# gtjennings_4.net
KiCad netlist of a schematic drawn in EAGLE
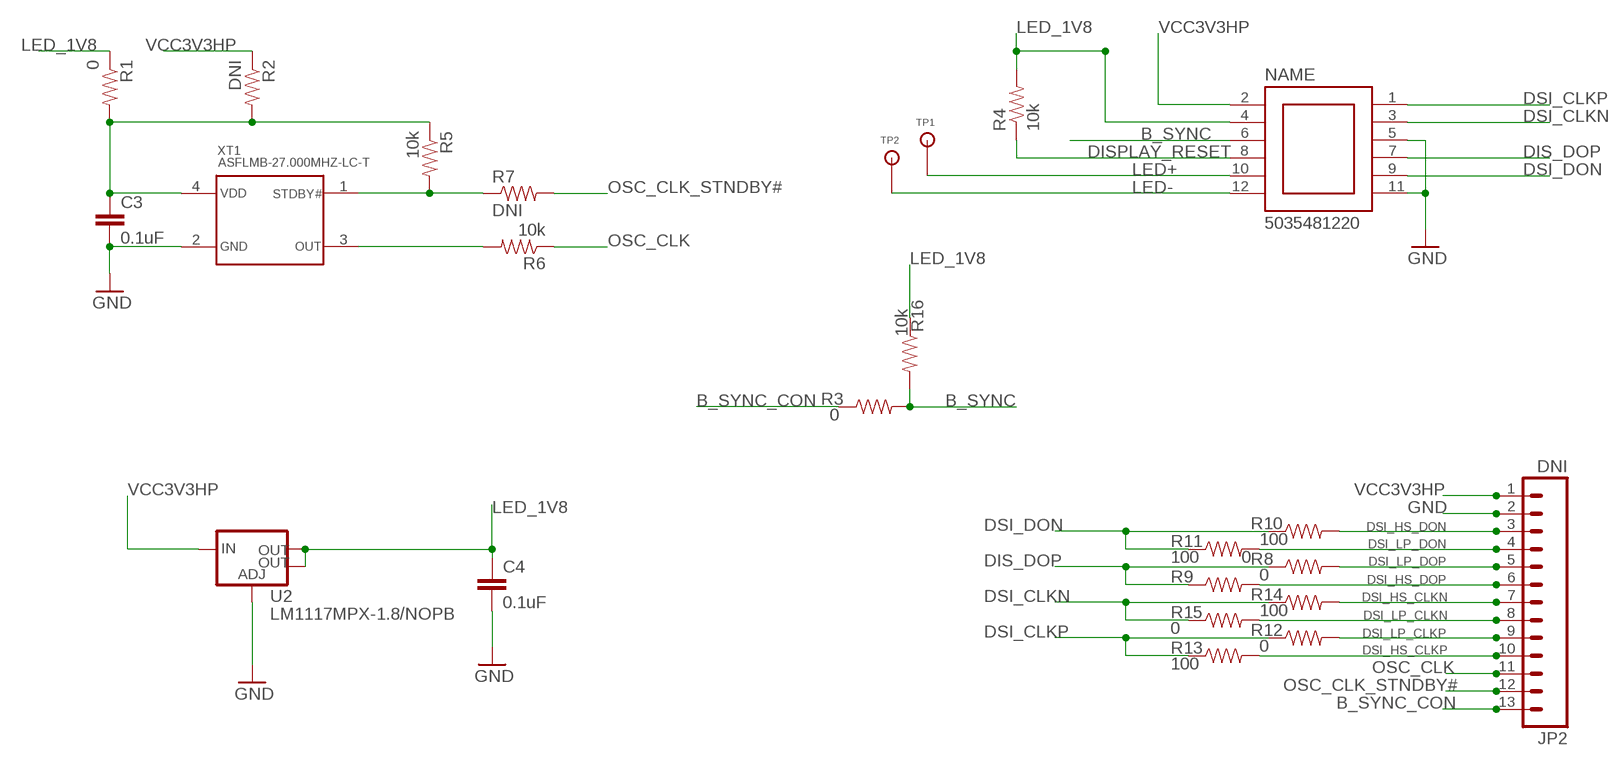
[diagram p0: schematic, sheet 1]

(export (version "E")
  (design (tool "Eeschema 10.0.6"))
  (components
    (comp (ref "C3")
      (value "0.1uF")
      (footprint "eagle-import:0402-CAP")
      (libsource (lib "eagle-import") (part "CAP0402-CAP"))
    )
    (comp (ref "C4")
      (value "0.1uF")
      (footprint "eagle-import:0402-CAP")
      (libsource (lib "eagle-import") (part "CAP0402-CAP"))
    )
    (comp (ref "JP1")
      (value "5035481220")
      (footprint "eagle-import:5035481220")
      (libsource (lib "eagle-import") (part "5035481220"))
    )
    (comp (ref "JP2")
      (value "DNI")
      (footprint "eagle-import:1X13")
      (libsource (lib "eagle-import") (part "M13"))
    )
    (comp (ref "R1")
      (value "0")
      (footprint "eagle-import:0402-RES")
      (libsource (lib "eagle-import") (part "RESISTOR0402"))
    )
    (comp (ref "R2")
      (value "DNI")
      (footprint "eagle-import:0402-RES")
      (libsource (lib "eagle-import") (part "RESISTOR0402"))
    )
    (comp (ref "R3")
      (value "0")
      (footprint "eagle-import:0402-RES")
      (libsource (lib "eagle-import") (part "RESISTOR0402"))
    )
    (comp (ref "R4")
      (value "10k")
      (footprint "eagle-import:0402-RES")
      (libsource (lib "eagle-import") (part "RESISTOR0402"))
    )
    (comp (ref "R5")
      (value "10k")
      (footprint "eagle-import:0402-RES")
      (libsource (lib "eagle-import") (part "RESISTOR0402"))
    )
    (comp (ref "R6")
      (value "10k")
      (footprint "eagle-import:0402-RES")
      (libsource (lib "eagle-import") (part "RESISTOR0402"))
    )
    (comp (ref "R7")
      (value "DNI")
      (footprint "eagle-import:0402-RES")
      (libsource (lib "eagle-import") (part "RESISTOR0402"))
    )
    (comp (ref "R8")
      (value "0")
      (footprint "eagle-import:0402-RES")
      (libsource (lib "eagle-import") (part "RESISTOR0402"))
    )
    (comp (ref "R9")
      (value "100")
      (footprint "eagle-import:0402-RES")
      (libsource (lib "eagle-import") (part "RESISTOR0402"))
    )
    (comp (ref "R10")
      (value "100")
      (footprint "eagle-import:0402-RES")
      (libsource (lib "eagle-import") (part "RESISTOR0402"))
    )
    (comp (ref "R11")
      (value "0")
      (footprint "eagle-import:0402-RES")
      (libsource (lib "eagle-import") (part "RESISTOR0402"))
    )
    (comp (ref "R12")
      (value "0")
      (footprint "eagle-import:0402-RES")
      (libsource (lib "eagle-import") (part "RESISTOR0402"))
    )
    (comp (ref "R13")
      (value "100")
      (footprint "eagle-import:0402-RES")
      (libsource (lib "eagle-import") (part "RESISTOR0402"))
    )
    (comp (ref "R14")
      (value "100")
      (footprint "eagle-import:0402-RES")
      (libsource (lib "eagle-import") (part "RESISTOR0402"))
    )
    (comp (ref "R15")
      (value "0")
      (footprint "eagle-import:0402-RES")
      (libsource (lib "eagle-import") (part "RESISTOR0402"))
    )
    (comp (ref "R16")
      (value "10k")
      (footprint "eagle-import:0402-RES")
      (libsource (lib "eagle-import") (part "RESISTOR0402"))
    )
    (comp (ref "TP1") (value "TP") (footprint "eagle-import:TP") (libsource (lib "eagle-import") (part "TP")))
    (comp (ref "TP2") (value "TP") (footprint "eagle-import:TP") (libsource (lib "eagle-import") (part "TP")))
    (comp (ref "U2")
      (value "LM1117MPX-1.8/NOPB")
      (footprint "eagle-import:SOT223")
      (libsource (lib "eagle-import") (part "V_REG_LM1117SOT223"))
    )
    (comp (ref "XT1")
      (value "ASFLMB-27.000MHZ-LC-T")
      (footprint "eagle-import:ASFLMB-27.000MHZ-LC-T")
      (libsource (lib "eagle-import") (part "ASFLMB-27.000MHZ-LC-T"))
    )
  )
  (nets
    (net (code "1") (name "/B_SYNC") (class "Default")
      (node (ref "JP1") (pin "6") (pinfunction "6_6") (pintype "bidirectional"))
      (node (ref "R16") (pin "2") (pinfunction "2_2") (pintype "passive"))
      (node (ref "R3") (pin "2") (pinfunction "2_2") (pintype "passive"))
    )
    (net (code "2") (name "/B_SYNC_CON") (class "Default")
      (node (ref "JP2") (pin "13") (pinfunction "13_13") (pintype "passive"))
      (node (ref "R3") (pin "1") (pinfunction "1_1") (pintype "passive"))
    )
    (net (code "3") (name "/DISPLAY_RESET") (class "Default")
      (node (ref "JP1") (pin "8") (pinfunction "8_8") (pintype "bidirectional"))
      (node (ref "R4") (pin "1") (pinfunction "1_1") (pintype "passive"))
    )
    (net (code "4") (name "/DIS_DOP") (class "Default")
      (node (ref "JP1") (pin "7") (pinfunction "7_7") (pintype "bidirectional"))
      (node (ref "R8") (pin "1") (pinfunction "1_1") (pintype "passive"))
      (node (ref "R9") (pin "1") (pinfunction "1_1") (pintype "passive"))
    )
    (net (code "5") (name "/DSI_CLKN") (class "Default")
      (node (ref "JP1") (pin "3") (pinfunction "3_3") (pintype "bidirectional"))
      (node (ref "R14") (pin "1") (pinfunction "1_1") (pintype "passive"))
      (node (ref "R15") (pin "1") (pinfunction "1_1") (pintype "passive"))
    )
    (net (code "6") (name "/DSI_CLKP") (class "Default")
      (node (ref "JP1") (pin "1") (pinfunction "1_1") (pintype "bidirectional"))
      (node (ref "R12") (pin "1") (pinfunction "1_1") (pintype "passive"))
      (node (ref "R13") (pin "1") (pinfunction "1_1") (pintype "passive"))
    )
    (net (code "7") (name "/DSI_DON") (class "Default")
      (node (ref "JP1") (pin "9") (pinfunction "9_9") (pintype "bidirectional"))
      (node (ref "R10") (pin "1") (pinfunction "1_1") (pintype "passive"))
      (node (ref "R11") (pin "1") (pinfunction "1_1") (pintype "passive"))
    )
    (net (code "8") (name "/DSI_HS_CLKN") (class "Default")
      (node (ref "JP2") (pin "7") (pinfunction "7_7") (pintype "passive"))
      (node (ref "R14") (pin "2") (pinfunction "2_2") (pintype "passive"))
    )
    (net (code "9") (name "/DSI_HS_CLKP") (class "Default")
      (node (ref "JP2") (pin "10") (pinfunction "10_10") (pintype "passive"))
      (node (ref "R13") (pin "2") (pinfunction "2_2") (pintype "passive"))
    )
    (net (code "10") (name "/DSI_HS_DON") (class "Default")
      (node (ref "JP2") (pin "3") (pinfunction "3_3") (pintype "passive"))
      (node (ref "R10") (pin "2") (pinfunction "2_2") (pintype "passive"))
    )
    (net (code "11") (name "/DSI_HS_DOP") (class "Default")
      (node (ref "JP2") (pin "6") (pinfunction "6_6") (pintype "passive"))
      (node (ref "R9") (pin "2") (pinfunction "2_2") (pintype "passive"))
    )
    (net (code "12") (name "/DSI_LP_CLKN") (class "Default")
      (node (ref "JP2") (pin "8") (pinfunction "8_8") (pintype "passive"))
      (node (ref "R15") (pin "2") (pinfunction "2_2") (pintype "passive"))
    )
    (net (code "13") (name "/DSI_LP_CLKP") (class "Default")
      (node (ref "JP2") (pin "9") (pinfunction "9_9") (pintype "passive"))
      (node (ref "R12") (pin "2") (pinfunction "2_2") (pintype "passive"))
    )
    (net (code "14") (name "/DSI_LP_DON") (class "Default")
      (node (ref "JP2") (pin "4") (pinfunction "4_4") (pintype "passive"))
      (node (ref "R11") (pin "2") (pinfunction "2_2") (pintype "passive"))
    )
    (net (code "15") (name "/DSI_LP_DOP") (class "Default")
      (node (ref "JP2") (pin "5") (pinfunction "5_5") (pintype "passive"))
      (node (ref "R8") (pin "2") (pinfunction "2_2") (pintype "passive"))
    )
    (net (code "16") (name "/LED+") (class "Default")
      (node (ref "JP1") (pin "10") (pinfunction "10_10") (pintype "bidirectional"))
      (node (ref "TP1") (pin "1") (pinfunction "1_1") (pintype "bidirectional"))
    )
    (net (code "17") (name "/LED-") (class "Default")
      (node (ref "JP1") (pin "12") (pinfunction "12_12") (pintype "bidirectional"))
      (node (ref "TP2") (pin "1") (pinfunction "1_1") (pintype "bidirectional"))
    )
    (net (code "18") (name "/LED_1V8") (class "Default")
      (node (ref "C4") (pin "1") (pinfunction "1_1") (pintype "passive"))
      (node (ref "JP1") (pin "4") (pinfunction "4_4") (pintype "bidirectional"))
      (node (ref "R1") (pin "1") (pinfunction "1_1") (pintype "passive"))
      (node (ref "R16") (pin "1") (pinfunction "1_1") (pintype "passive"))
      (node (ref "R4") (pin "2") (pinfunction "2_2") (pintype "passive"))
      (node (ref "U2") (pin "2") (pinfunction "OUT_2") (pintype "output"))
      (node (ref "U2") (pin "4") (pinfunction "OUT_4") (pintype "output"))
    )
    (net (code "19") (name "/OSC_CLK") (class "Default")
      (node (ref "JP2") (pin "11") (pinfunction "11_11") (pintype "passive"))
      (node (ref "R6") (pin "1") (pinfunction "1_1") (pintype "passive"))
    )
    (net (code "20") (name "/OSC_CLK_STNDBY#") (class "Default")
      (node (ref "JP2") (pin "12") (pinfunction "12_12") (pintype "passive"))
      (node (ref "R7") (pin "2") (pinfunction "2_2") (pintype "passive"))
    )
    (net (code "21") (name "/VCC3V3HP") (class "Default")
      (node (ref "JP1") (pin "2") (pinfunction "2_2") (pintype "bidirectional"))
      (node (ref "JP2") (pin "1") (pinfunction "1_1") (pintype "passive"))
      (node (ref "R2") (pin "1") (pinfunction "1_1") (pintype "passive"))
      (node (ref "U2") (pin "3") (pinfunction "IN_3") (pintype "input"))
    )
    (net (code "22") (name "GND") (class "Default")
      (node (ref "C3") (pin "2") (pinfunction "2_2") (pintype "passive"))
      (node (ref "C4") (pin "2") (pinfunction "2_2") (pintype "passive"))
      (node (ref "JP1") (pin "11") (pinfunction "11_11") (pintype "bidirectional"))
      (node (ref "JP1") (pin "5") (pinfunction "5_5") (pintype "bidirectional"))
      (node (ref "JP2") (pin "2") (pinfunction "2_2") (pintype "passive"))
      (node (ref "U2") (pin "1") (pinfunction "ADJ_1") (pintype "input"))
      (node (ref "XT1") (pin "2") (pinfunction "2_2") (pintype "bidirectional"))
    )
    (net (code "23") (name "Net-(C3-Pad1)") (class "Default")
      (node (ref "C3") (pin "1") (pinfunction "1_1") (pintype "passive"))
      (node (ref "R1") (pin "2") (pinfunction "2_2") (pintype "passive"))
      (node (ref "R2") (pin "2") (pinfunction "2_2") (pintype "passive"))
      (node (ref "R5") (pin "1") (pinfunction "1_1") (pintype "passive"))
      (node (ref "XT1") (pin "4") (pinfunction "4_4") (pintype "bidirectional"))
    )
    (net (code "24") (name "Net-(R5-Pad2)") (class "Default")
      (node (ref "R5") (pin "2") (pinfunction "2_2") (pintype "passive"))
      (node (ref "R7") (pin "1") (pinfunction "1_1") (pintype "passive"))
      (node (ref "XT1") (pin "1") (pinfunction "1_1") (pintype "bidirectional"))
    )
    (net (code "25") (name "Net-(R6-Pad2)") (class "Default")
      (node (ref "R6") (pin "2") (pinfunction "2_2") (pintype "passive"))
      (node (ref "XT1") (pin "3") (pinfunction "3_3") (pintype "bidirectional"))
    )
  )
)
